# biochem.net
KiCad netlist of a schematic drawn in EAGLE
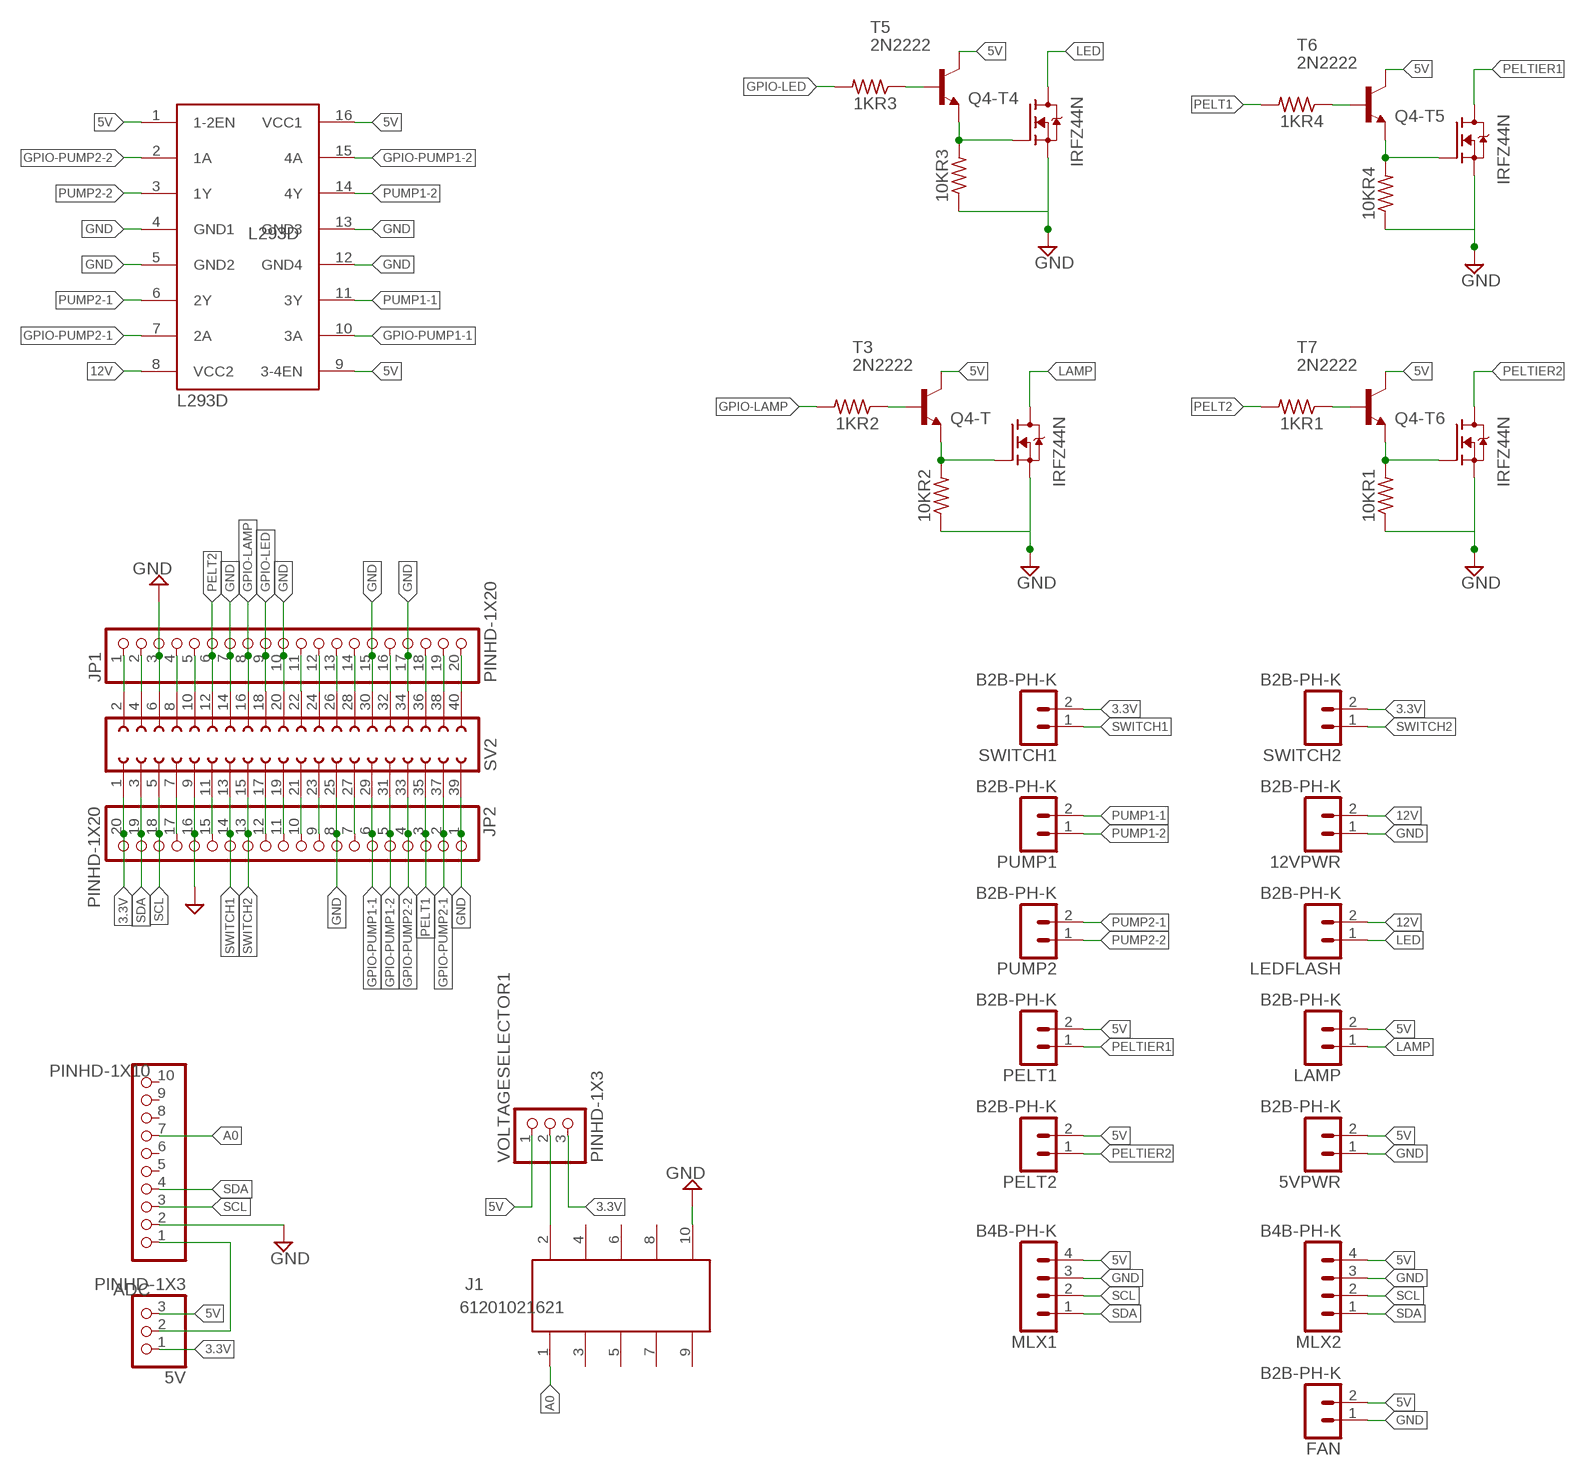
[diagram p0: schematic, sheet 1]

(export (version "E")
  (design (tool "Eeschema 10.0.6"))
  (components
    (comp (ref "1KR1")
      (value "R-US_0204/7")
      (footprint "eagle-import:0204_7")
      (libsource (lib "eagle-import") (part "R-US_0204/7"))
    )
    (comp (ref "1KR2")
      (value "R-US_0204/7")
      (footprint "eagle-import:0204_7")
      (libsource (lib "eagle-import") (part "R-US_0204/7"))
    )
    (comp (ref "1KR3")
      (value "R-US_0204/7")
      (footprint "eagle-import:0204_7")
      (libsource (lib "eagle-import") (part "R-US_0204/7"))
    )
    (comp (ref "1KR4")
      (value "R-US_0204/7")
      (footprint "eagle-import:0204_7")
      (libsource (lib "eagle-import") (part "R-US_0204/7"))
    )
    (comp (ref "5V")
      (value "PINHD-1X3")
      (footprint "eagle-import:1X03")
      (libsource (lib "eagle-import") (part "PINHD-1X3"))
    )
    (comp (ref "5VPWR")
      (value "B2B-PH-K")
      (footprint "eagle-import:B2B-PH-K")
      (fields (field (name "MF") "JST Corporation"))
      (libsource (lib "eagle-import") (part "B2B-PH-K"))
    )
    (comp (ref "10KR1")
      (value "R-US_0204/7")
      (footprint "eagle-import:0204_7")
      (libsource (lib "eagle-import") (part "R-US_0204/7"))
    )
    (comp (ref "10KR2")
      (value "R-US_0204/7")
      (footprint "eagle-import:0204_7")
      (libsource (lib "eagle-import") (part "R-US_0204/7"))
    )
    (comp (ref "10KR3")
      (value "R-US_0204/7")
      (footprint "eagle-import:0204_7")
      (libsource (lib "eagle-import") (part "R-US_0204/7"))
    )
    (comp (ref "10KR4")
      (value "R-US_0204/7")
      (footprint "eagle-import:0204_7")
      (libsource (lib "eagle-import") (part "R-US_0204/7"))
    )
    (comp (ref "12VPWR")
      (value "B2B-PH-K")
      (footprint "eagle-import:B2B-PH-K")
      (fields (field (name "MF") "JST Corporation"))
      (libsource (lib "eagle-import") (part "B2B-PH-K"))
    )
    (comp (ref "ADC")
      (value "PINHD-1X10")
      (footprint "eagle-import:1X10")
      (libsource (lib "eagle-import") (part "PINHD-1X10"))
    )
    (comp (ref "FAN")
      (value "B2B-PH-K")
      (footprint "eagle-import:B2B-PH-K")
      (fields (field (name "MF") "JST Corporation"))
      (libsource (lib "eagle-import") (part "B2B-PH-K"))
    )
    (comp (ref "J1")
      (value "61201021621")
      (footprint "eagle-import:61201021621")
      (fields (field (name "MF") "Wurth Elektronik"))
      (libsource (lib "eagle-import") (part "61201021621"))
    )
    (comp (ref "JP1")
      (value "PINHD-1X20")
      (footprint "eagle-import:1X20")
      (libsource (lib "eagle-import") (part "PINHD-1X20"))
    )
    (comp (ref "JP2")
      (value "PINHD-1X20")
      (footprint "eagle-import:1X20")
      (libsource (lib "eagle-import") (part "PINHD-1X20"))
    )
    (comp (ref "L293D")
      (value "L293D")
      (footprint "eagle-import:DIL16")
      (libsource (lib "eagle-import") (part "L293D"))
    )
    (comp (ref "LAMP")
      (value "B2B-PH-K")
      (footprint "eagle-import:B2B-PH-K")
      (fields (field (name "MF") "JST Corporation"))
      (libsource (lib "eagle-import") (part "B2B-PH-K"))
    )
    (comp (ref "LEDFLASH")
      (value "B2B-PH-K")
      (footprint "eagle-import:B2B-PH-K")
      (fields (field (name "MF") "JST Corporation"))
      (libsource (lib "eagle-import") (part "B2B-PH-K"))
    )
    (comp (ref "MLX1")
      (value "B4B-PH-K")
      (footprint "eagle-import:B4B-PH-K")
      (libsource (lib "eagle-import") (part "B4B-PH-K"))
    )
    (comp (ref "MLX2")
      (value "B4B-PH-K")
      (footprint "eagle-import:B4B-PH-K")
      (libsource (lib "eagle-import") (part "B4B-PH-K"))
    )
    (comp (ref "PELT1")
      (value "B2B-PH-K")
      (footprint "eagle-import:B2B-PH-K")
      (fields (field (name "MF") "JST Corporation"))
      (libsource (lib "eagle-import") (part "B2B-PH-K"))
    )
    (comp (ref "PELT2")
      (value "B2B-PH-K")
      (footprint "eagle-import:B2B-PH-K")
      (fields (field (name "MF") "JST Corporation"))
      (libsource (lib "eagle-import") (part "B2B-PH-K"))
    )
    (comp (ref "PUMP1")
      (value "B2B-PH-K")
      (footprint "eagle-import:B2B-PH-K")
      (fields (field (name "MF") "JST Corporation"))
      (libsource (lib "eagle-import") (part "B2B-PH-K"))
    )
    (comp (ref "PUMP2")
      (value "B2B-PH-K")
      (footprint "eagle-import:B2B-PH-K")
      (fields (field (name "MF") "JST Corporation"))
      (libsource (lib "eagle-import") (part "B2B-PH-K"))
    )
    (comp (ref "Q4-T")
      (value "IRFZ44N")
      (footprint "eagle-import:TO254P1016X419X2286-3")
      (fields (field (name "MF") "Infineon Technologies"))
      (libsource (lib "eagle-import") (part "IRFZ44N"))
    )
    (comp (ref "Q4-T4")
      (value "IRFZ44N")
      (footprint "eagle-import:TO254P1016X419X2286-3")
      (fields (field (name "MF") "Infineon Technologies"))
      (libsource (lib "eagle-import") (part "IRFZ44N"))
    )
    (comp (ref "Q4-T5")
      (value "IRFZ44N")
      (footprint "eagle-import:TO254P1016X419X2286-3")
      (fields (field (name "MF") "Infineon Technologies"))
      (libsource (lib "eagle-import") (part "IRFZ44N"))
    )
    (comp (ref "Q4-T6")
      (value "IRFZ44N")
      (footprint "eagle-import:TO254P1016X419X2286-3")
      (fields (field (name "MF") "Infineon Technologies"))
      (libsource (lib "eagle-import") (part "IRFZ44N"))
    )
    (comp (ref "SV2")
      (value "FE20-2")
      (footprint "eagle-import:FE20-2")
      (libsource (lib "eagle-import") (part "FE20-2"))
    )
    (comp (ref "SWITCH1")
      (value "B2B-PH-K")
      (footprint "eagle-import:B2B-PH-K")
      (fields (field (name "MF") "JST Corporation"))
      (libsource (lib "eagle-import") (part "B2B-PH-K"))
    )
    (comp (ref "SWITCH2")
      (value "B2B-PH-K")
      (footprint "eagle-import:B2B-PH-K")
      (fields (field (name "MF") "JST Corporation"))
      (libsource (lib "eagle-import") (part "B2B-PH-K"))
    )
    (comp (ref "T3")
      (value "2N2222")
      (footprint "eagle-import:TO92-EBC-OVAL")
      (libsource (lib "eagle-import") (part "2N2222"))
    )
    (comp (ref "T5")
      (value "2N2222")
      (footprint "eagle-import:TO92-EBC-OVAL")
      (libsource (lib "eagle-import") (part "2N2222"))
    )
    (comp (ref "T6")
      (value "2N2222")
      (footprint "eagle-import:TO92-EBC-OVAL")
      (libsource (lib "eagle-import") (part "2N2222"))
    )
    (comp (ref "T7")
      (value "2N2222")
      (footprint "eagle-import:TO92-EBC-OVAL")
      (libsource (lib "eagle-import") (part "2N2222"))
    )
    (comp (ref "VOLTAGESELECTOR1")
      (value "PINHD-1X3")
      (footprint "eagle-import:1X03")
      (libsource (lib "eagle-import") (part "PINHD-1X3"))
    )
  )
  (nets
    (net (code "1") (name "3.3V") (class "Default")
      (node (ref "5V") (pin "1") (pinfunction "1_1") (pintype "passive"))
      (node (ref "JP2") (pin "20") (pinfunction "20_20") (pintype "passive"))
      (node (ref "SV2") (pin "1") (pinfunction "1_1") (pintype "passive"))
      (node (ref "SWITCH1") (pin "2") (pinfunction "2_2") (pintype "passive"))
      (node (ref "SWITCH2") (pin "2") (pinfunction "2_2") (pintype "passive"))
      (node (ref "VOLTAGESELECTOR1") (pin "3") (pinfunction "3_3") (pintype "passive"))
    )
    (net (code "2") (name "5V") (class "Default")
      (node (ref "5V") (pin "3") (pinfunction "3_3") (pintype "passive"))
      (node (ref "5VPWR") (pin "2") (pinfunction "2_2") (pintype "passive"))
      (node (ref "FAN") (pin "2") (pinfunction "2_2") (pintype "passive"))
      (node (ref "L293D") (pin "1") (pinfunction "1-2EN_1") (pintype "input"))
      (node (ref "L293D") (pin "16") (pinfunction "VCC1_16") (pintype "power_in"))
      (node (ref "L293D") (pin "9") (pinfunction "3-4EN_9") (pintype "input"))
      (node (ref "LAMP") (pin "2") (pinfunction "2_2") (pintype "passive"))
      (node (ref "MLX1") (pin "4") (pinfunction "4_4") (pintype "passive"))
      (node (ref "MLX2") (pin "4") (pinfunction "4_4") (pintype "passive"))
      (node (ref "PELT1") (pin "2") (pinfunction "2_2") (pintype "passive"))
      (node (ref "PELT2") (pin "2") (pinfunction "2_2") (pintype "passive"))
      (node (ref "T3") (pin "C") (pinfunction "C_C") (pintype "passive"))
      (node (ref "T5") (pin "C") (pinfunction "C_C") (pintype "passive"))
      (node (ref "T6") (pin "C") (pinfunction "C_C") (pintype "passive"))
      (node (ref "T7") (pin "C") (pinfunction "C_C") (pintype "passive"))
      (node (ref "VOLTAGESELECTOR1") (pin "1") (pinfunction "1_1") (pintype "passive"))
    )
    (net (code "3") (name "12V") (class "Default")
      (node (ref "12VPWR") (pin "2") (pinfunction "2_2") (pintype "passive"))
      (node (ref "L293D") (pin "8") (pinfunction "VCC2_8") (pintype "power_in"))
      (node (ref "LEDFLASH") (pin "2") (pinfunction "2_2") (pintype "passive"))
    )
    (net (code "4") (name "A0") (class "Default")
      (node (ref "ADC") (pin "7") (pinfunction "7_7") (pintype "passive"))
      (node (ref "J1") (pin "1") (pinfunction "1_1") (pintype "passive"))
    )
    (net (code "5") (name "GND") (class "Default")
      (node (ref "10KR1") (pin "1") (pinfunction "1_1") (pintype "passive"))
      (node (ref "10KR2") (pin "1") (pinfunction "1_1") (pintype "passive"))
      (node (ref "10KR3") (pin "1") (pinfunction "1_1") (pintype "passive"))
      (node (ref "10KR4") (pin "1") (pinfunction "1_1") (pintype "passive"))
      (node (ref "12VPWR") (pin "1") (pinfunction "1_1") (pintype "passive"))
      (node (ref "5VPWR") (pin "1") (pinfunction "1_1") (pintype "passive"))
      (node (ref "ADC") (pin "2") (pinfunction "2_2") (pintype "passive"))
      (node (ref "FAN") (pin "1") (pinfunction "1_1") (pintype "passive"))
      (node (ref "J1") (pin "10") (pinfunction "10_10") (pintype "passive"))
      (node (ref "JP1") (pin "10") (pinfunction "10_10") (pintype "passive"))
      (node (ref "JP1") (pin "15") (pinfunction "15_15") (pintype "passive"))
      (node (ref "JP1") (pin "17") (pinfunction "17_17") (pintype "passive"))
      (node (ref "JP1") (pin "3") (pinfunction "3_3") (pintype "passive"))
      (node (ref "JP1") (pin "7") (pinfunction "7_7") (pintype "passive"))
      (node (ref "JP2") (pin "1") (pinfunction "1_1") (pintype "passive"))
      (node (ref "JP2") (pin "16") (pinfunction "16_16") (pintype "passive"))
      (node (ref "JP2") (pin "8") (pinfunction "8_8") (pintype "passive"))
      (node (ref "L293D") (pin "12") (pinfunction "GND4_12") (pintype "power_in"))
      (node (ref "L293D") (pin "13") (pinfunction "GND3_13") (pintype "power_in"))
      (node (ref "L293D") (pin "4") (pinfunction "GND1_4") (pintype "power_in"))
      (node (ref "L293D") (pin "5") (pinfunction "GND2_5") (pintype "power_in"))
      (node (ref "MLX1") (pin "3") (pinfunction "3_3") (pintype "passive"))
      (node (ref "MLX2") (pin "3") (pinfunction "3_3") (pintype "passive"))
      (node (ref "Q4-T") (pin "3") (pinfunction "S_3") (pintype "passive"))
      (node (ref "Q4-T4") (pin "3") (pinfunction "S_3") (pintype "passive"))
      (node (ref "Q4-T5") (pin "3") (pinfunction "S_3") (pintype "passive"))
      (node (ref "Q4-T6") (pin "3") (pinfunction "S_3") (pintype "passive"))
      (node (ref "SV2") (pin "14") (pinfunction "14_14") (pintype "passive"))
      (node (ref "SV2") (pin "20") (pinfunction "20_20") (pintype "passive"))
      (node (ref "SV2") (pin "25") (pinfunction "25_25") (pintype "passive"))
      (node (ref "SV2") (pin "30") (pinfunction "30_30") (pintype "passive"))
      (node (ref "SV2") (pin "34") (pinfunction "34_34") (pintype "passive"))
      (node (ref "SV2") (pin "39") (pinfunction "39_39") (pintype "passive"))
      (node (ref "SV2") (pin "6") (pinfunction "6_6") (pintype "passive"))
      (node (ref "SV2") (pin "9") (pinfunction "9_9") (pintype "passive"))
    )
    (net (code "6") (name "GPIO-LAMP") (class "Default")
      (node (ref "1KR2") (pin "2") (pinfunction "2_2") (pintype "passive"))
      (node (ref "JP1") (pin "8") (pinfunction "8_8") (pintype "passive"))
      (node (ref "SV2") (pin "16") (pinfunction "16_16") (pintype "passive"))
    )
    (net (code "7") (name "GPIO-LED") (class "Default")
      (node (ref "1KR3") (pin "2") (pinfunction "2_2") (pintype "passive"))
      (node (ref "JP1") (pin "9") (pinfunction "9_9") (pintype "passive"))
      (node (ref "SV2") (pin "18") (pinfunction "18_18") (pintype "passive"))
    )
    (net (code "8") (name "GPIO-PUMP1-1") (class "Default")
      (node (ref "JP2") (pin "6") (pinfunction "6_6") (pintype "passive"))
      (node (ref "L293D") (pin "10") (pinfunction "3A_10") (pintype "input"))
      (node (ref "SV2") (pin "29") (pinfunction "29_29") (pintype "passive"))
    )
    (net (code "9") (name "GPIO-PUMP1-2") (class "Default")
      (node (ref "JP2") (pin "5") (pinfunction "5_5") (pintype "passive"))
      (node (ref "L293D") (pin "15") (pinfunction "4A_15") (pintype "input"))
      (node (ref "SV2") (pin "31") (pinfunction "31_31") (pintype "passive"))
    )
    (net (code "10") (name "GPIO-PUMP2-1") (class "Default")
      (node (ref "JP2") (pin "2") (pinfunction "2_2") (pintype "passive"))
      (node (ref "L293D") (pin "7") (pinfunction "2A_7") (pintype "input"))
      (node (ref "SV2") (pin "37") (pinfunction "37_37") (pintype "passive"))
    )
    (net (code "11") (name "GPIO-PUMP2-2") (class "Default")
      (node (ref "JP2") (pin "4") (pinfunction "4_4") (pintype "passive"))
      (node (ref "L293D") (pin "2") (pinfunction "1A_2") (pintype "input"))
      (node (ref "SV2") (pin "33") (pinfunction "33_33") (pintype "passive"))
    )
    (net (code "12") (name "LAMP") (class "Default")
      (node (ref "LAMP") (pin "1") (pinfunction "1_1") (pintype "passive"))
      (node (ref "Q4-T") (pin "2") (pinfunction "D_2") (pintype "passive"))
    )
    (net (code "13") (name "LED") (class "Default")
      (node (ref "LEDFLASH") (pin "1") (pinfunction "1_1") (pintype "passive"))
      (node (ref "Q4-T4") (pin "2") (pinfunction "D_2") (pintype "passive"))
    )
    (net (code "14") (name "Net-(1KR1-Pad1)") (class "Default")
      (node (ref "1KR1") (pin "1") (pinfunction "1_1") (pintype "passive"))
      (node (ref "T7") (pin "B") (pinfunction "B_B") (pintype "passive"))
    )
    (net (code "15") (name "Net-(1KR2-Pad1)") (class "Default")
      (node (ref "1KR2") (pin "1") (pinfunction "1_1") (pintype "passive"))
      (node (ref "T3") (pin "B") (pinfunction "B_B") (pintype "passive"))
    )
    (net (code "16") (name "Net-(1KR3-Pad1)") (class "Default")
      (node (ref "1KR3") (pin "1") (pinfunction "1_1") (pintype "passive"))
      (node (ref "T5") (pin "B") (pinfunction "B_B") (pintype "passive"))
    )
    (net (code "17") (name "Net-(1KR4-Pad1)") (class "Default")
      (node (ref "1KR4") (pin "1") (pinfunction "1_1") (pintype "passive"))
      (node (ref "T6") (pin "B") (pinfunction "B_B") (pintype "passive"))
    )
    (net (code "18") (name "Net-(5V-Pad2)") (class "Default")
      (node (ref "5V") (pin "2") (pinfunction "2_2") (pintype "passive"))
      (node (ref "ADC") (pin "1") (pinfunction "1_1") (pintype "passive"))
    )
    (net (code "19") (name "Net-(J1-Pad2)") (class "Default")
      (node (ref "J1") (pin "2") (pinfunction "2_2") (pintype "passive"))
      (node (ref "VOLTAGESELECTOR1") (pin "2") (pinfunction "2_2") (pintype "passive"))
    )
    (net (code "20") (name "Net-(JP1-Pad1)") (class "Default")
      (node (ref "JP1") (pin "1") (pinfunction "1_1") (pintype "passive"))
      (node (ref "SV2") (pin "2") (pinfunction "2_2") (pintype "passive"))
    )
    (net (code "21") (name "Net-(JP1-Pad2)") (class "Default")
      (node (ref "JP1") (pin "2") (pinfunction "2_2") (pintype "passive"))
      (node (ref "SV2") (pin "4") (pinfunction "4_4") (pintype "passive"))
    )
    (net (code "22") (name "Net-(JP1-Pad4)") (class "Default")
      (node (ref "JP1") (pin "4") (pinfunction "4_4") (pintype "passive"))
      (node (ref "SV2") (pin "8") (pinfunction "8_8") (pintype "passive"))
    )
    (net (code "23") (name "Net-(JP1-Pad5)") (class "Default")
      (node (ref "JP1") (pin "5") (pinfunction "5_5") (pintype "passive"))
      (node (ref "SV2") (pin "10") (pinfunction "10_10") (pintype "passive"))
    )
    (net (code "24") (name "Net-(JP1-Pad11)") (class "Default")
      (node (ref "JP1") (pin "11") (pinfunction "11_11") (pintype "passive"))
      (node (ref "SV2") (pin "22") (pinfunction "22_22") (pintype "passive"))
    )
    (net (code "25") (name "Net-(JP1-Pad12)") (class "Default")
      (node (ref "JP1") (pin "12") (pinfunction "12_12") (pintype "passive"))
      (node (ref "SV2") (pin "24") (pinfunction "24_24") (pintype "passive"))
    )
    (net (code "26") (name "Net-(JP1-Pad13)") (class "Default")
      (node (ref "JP1") (pin "13") (pinfunction "13_13") (pintype "passive"))
      (node (ref "SV2") (pin "26") (pinfunction "26_26") (pintype "passive"))
    )
    (net (code "27") (name "Net-(JP1-Pad14)") (class "Default")
      (node (ref "JP1") (pin "14") (pinfunction "14_14") (pintype "passive"))
      (node (ref "SV2") (pin "28") (pinfunction "28_28") (pintype "passive"))
    )
    (net (code "28") (name "Net-(JP1-Pad16)") (class "Default")
      (node (ref "JP1") (pin "16") (pinfunction "16_16") (pintype "passive"))
      (node (ref "SV2") (pin "32") (pinfunction "32_32") (pintype "passive"))
    )
    (net (code "29") (name "Net-(JP1-Pad18)") (class "Default")
      (node (ref "JP1") (pin "18") (pinfunction "18_18") (pintype "passive"))
      (node (ref "SV2") (pin "36") (pinfunction "36_36") (pintype "passive"))
    )
    (net (code "30") (name "Net-(JP1-Pad19)") (class "Default")
      (node (ref "JP1") (pin "19") (pinfunction "19_19") (pintype "passive"))
      (node (ref "SV2") (pin "38") (pinfunction "38_38") (pintype "passive"))
    )
    (net (code "31") (name "Net-(JP1-Pad20)") (class "Default")
      (node (ref "JP1") (pin "20") (pinfunction "20_20") (pintype "passive"))
      (node (ref "SV2") (pin "40") (pinfunction "40_40") (pintype "passive"))
    )
    (net (code "32") (name "Net-(JP2-Pad7)") (class "Default")
      (node (ref "JP2") (pin "7") (pinfunction "7_7") (pintype "passive"))
      (node (ref "SV2") (pin "27") (pinfunction "27_27") (pintype "passive"))
    )
    (net (code "33") (name "Net-(JP2-Pad9)") (class "Default")
      (node (ref "JP2") (pin "9") (pinfunction "9_9") (pintype "passive"))
      (node (ref "SV2") (pin "23") (pinfunction "23_23") (pintype "passive"))
    )
    (net (code "34") (name "Net-(JP2-Pad10)") (class "Default")
      (node (ref "JP2") (pin "10") (pinfunction "10_10") (pintype "passive"))
      (node (ref "SV2") (pin "21") (pinfunction "21_21") (pintype "passive"))
    )
    (net (code "35") (name "Net-(JP2-Pad11)") (class "Default")
      (node (ref "JP2") (pin "11") (pinfunction "11_11") (pintype "passive"))
      (node (ref "SV2") (pin "19") (pinfunction "19_19") (pintype "passive"))
    )
    (net (code "36") (name "Net-(JP2-Pad12)") (class "Default")
      (node (ref "JP2") (pin "12") (pinfunction "12_12") (pintype "passive"))
      (node (ref "SV2") (pin "17") (pinfunction "17_17") (pintype "passive"))
    )
    (net (code "37") (name "Net-(JP2-Pad15)") (class "Default")
      (node (ref "JP2") (pin "15") (pinfunction "15_15") (pintype "passive"))
      (node (ref "SV2") (pin "11") (pinfunction "11_11") (pintype "passive"))
    )
    (net (code "38") (name "Net-(JP2-Pad17)") (class "Default")
      (node (ref "JP2") (pin "17") (pinfunction "17_17") (pintype "passive"))
      (node (ref "SV2") (pin "7") (pinfunction "7_7") (pintype "passive"))
    )
    (net (code "39") (name "Net-(Q4-T-G)") (class "Default")
      (node (ref "10KR2") (pin "2") (pinfunction "2_2") (pintype "passive"))
      (node (ref "Q4-T") (pin "1") (pinfunction "G_1") (pintype "passive"))
      (node (ref "T3") (pin "E") (pinfunction "E_E") (pintype "passive"))
    )
    (net (code "40") (name "Net-(Q4-T4-G)") (class "Default")
      (node (ref "10KR3") (pin "2") (pinfunction "2_2") (pintype "passive"))
      (node (ref "Q4-T4") (pin "1") (pinfunction "G_1") (pintype "passive"))
      (node (ref "T5") (pin "E") (pinfunction "E_E") (pintype "passive"))
    )
    (net (code "41") (name "Net-(Q4-T5-G)") (class "Default")
      (node (ref "10KR4") (pin "2") (pinfunction "2_2") (pintype "passive"))
      (node (ref "Q4-T5") (pin "1") (pinfunction "G_1") (pintype "passive"))
      (node (ref "T6") (pin "E") (pinfunction "E_E") (pintype "passive"))
    )
    (net (code "42") (name "Net-(Q4-T6-G)") (class "Default")
      (node (ref "10KR1") (pin "2") (pinfunction "2_2") (pintype "passive"))
      (node (ref "Q4-T6") (pin "1") (pinfunction "G_1") (pintype "passive"))
      (node (ref "T7") (pin "E") (pinfunction "E_E") (pintype "passive"))
    )
    (net (code "43") (name "PELT1") (class "Default")
      (node (ref "1KR4") (pin "2") (pinfunction "2_2") (pintype "passive"))
      (node (ref "JP2") (pin "3") (pinfunction "3_3") (pintype "passive"))
      (node (ref "SV2") (pin "35") (pinfunction "35_35") (pintype "passive"))
    )
    (net (code "44") (name "PELT2") (class "Default")
      (node (ref "1KR1") (pin "2") (pinfunction "2_2") (pintype "passive"))
      (node (ref "JP1") (pin "6") (pinfunction "6_6") (pintype "passive"))
      (node (ref "SV2") (pin "12") (pinfunction "12_12") (pintype "passive"))
    )
    (net (code "45") (name "PELTIER1") (class "Default")
      (node (ref "PELT1") (pin "1") (pinfunction "1_1") (pintype "passive"))
      (node (ref "Q4-T5") (pin "2") (pinfunction "D_2") (pintype "passive"))
    )
    (net (code "46") (name "PELTIER2") (class "Default")
      (node (ref "PELT2") (pin "1") (pinfunction "1_1") (pintype "passive"))
      (node (ref "Q4-T6") (pin "2") (pinfunction "D_2") (pintype "passive"))
    )
    (net (code "47") (name "PUMP1-1") (class "Default")
      (node (ref "L293D") (pin "11") (pinfunction "3Y_11") (pintype "output"))
      (node (ref "PUMP1") (pin "2") (pinfunction "2_2") (pintype "passive"))
    )
    (net (code "48") (name "PUMP1-2") (class "Default")
      (node (ref "L293D") (pin "14") (pinfunction "4Y_14") (pintype "output"))
      (node (ref "PUMP1") (pin "1") (pinfunction "1_1") (pintype "passive"))
    )
    (net (code "49") (name "PUMP2-1") (class "Default")
      (node (ref "L293D") (pin "6") (pinfunction "2Y_6") (pintype "output"))
      (node (ref "PUMP2") (pin "2") (pinfunction "2_2") (pintype "passive"))
    )
    (net (code "50") (name "PUMP2-2") (class "Default")
      (node (ref "L293D") (pin "3") (pinfunction "1Y_3") (pintype "output"))
      (node (ref "PUMP2") (pin "1") (pinfunction "1_1") (pintype "passive"))
    )
    (net (code "51") (name "SCL") (class "Default")
      (node (ref "ADC") (pin "3") (pinfunction "3_3") (pintype "passive"))
      (node (ref "JP2") (pin "18") (pinfunction "18_18") (pintype "passive"))
      (node (ref "MLX1") (pin "2") (pinfunction "2_2") (pintype "passive"))
      (node (ref "MLX2") (pin "2") (pinfunction "2_2") (pintype "passive"))
      (node (ref "SV2") (pin "5") (pinfunction "5_5") (pintype "passive"))
    )
    (net (code "52") (name "SDA") (class "Default")
      (node (ref "ADC") (pin "4") (pinfunction "4_4") (pintype "passive"))
      (node (ref "JP2") (pin "19") (pinfunction "19_19") (pintype "passive"))
      (node (ref "MLX1") (pin "1") (pinfunction "1_1") (pintype "passive"))
      (node (ref "MLX2") (pin "1") (pinfunction "1_1") (pintype "passive"))
      (node (ref "SV2") (pin "3") (pinfunction "3_3") (pintype "passive"))
    )
    (net (code "53") (name "SWITCH1") (class "Default")
      (node (ref "JP2") (pin "14") (pinfunction "14_14") (pintype "passive"))
      (node (ref "SV2") (pin "13") (pinfunction "13_13") (pintype "passive"))
      (node (ref "SWITCH1") (pin "1") (pinfunction "1_1") (pintype "passive"))
    )
    (net (code "54") (name "SWITCH2") (class "Default")
      (node (ref "JP2") (pin "13") (pinfunction "13_13") (pintype "passive"))
      (node (ref "SV2") (pin "15") (pinfunction "15_15") (pintype "passive"))
      (node (ref "SWITCH2") (pin "1") (pinfunction "1_1") (pintype "passive"))
    )
    (net (code "55") (name "unconnected-(ADC-Pad5)") (class "Default")
      (node (ref "ADC") (pin "5") (pinfunction "5_5") (pintype "passive"))
    )
    (net (code "56") (name "unconnected-(ADC-Pad6)") (class "Default")
      (node (ref "ADC") (pin "6") (pinfunction "6_6") (pintype "passive"))
    )
    (net (code "57") (name "unconnected-(ADC-Pad8)") (class "Default")
      (node (ref "ADC") (pin "8") (pinfunction "8_8") (pintype "passive"))
    )
    (net (code "58") (name "unconnected-(ADC-Pad9)") (class "Default")
      (node (ref "ADC") (pin "9") (pinfunction "9_9") (pintype "passive"))
    )
    (net (code "59") (name "unconnected-(ADC-Pad10)") (class "Default")
      (node (ref "ADC") (pin "10") (pinfunction "10_10") (pintype "passive"))
    )
    (net (code "60") (name "unconnected-(J1-Pad3)") (class "Default")
      (node (ref "J1") (pin "3") (pinfunction "3_3") (pintype "passive"))
    )
    (net (code "61") (name "unconnected-(J1-Pad4)") (class "Default")
      (node (ref "J1") (pin "4") (pinfunction "4_4") (pintype "passive"))
    )
    (net (code "62") (name "unconnected-(J1-Pad5)") (class "Default")
      (node (ref "J1") (pin "5") (pinfunction "5_5") (pintype "passive"))
    )
    (net (code "63") (name "unconnected-(J1-Pad6)") (class "Default")
      (node (ref "J1") (pin "6") (pinfunction "6_6") (pintype "passive"))
    )
    (net (code "64") (name "unconnected-(J1-Pad7)") (class "Default")
      (node (ref "J1") (pin "7") (pinfunction "7_7") (pintype "passive"))
    )
    (net (code "65") (name "unconnected-(J1-Pad8)") (class "Default")
      (node (ref "J1") (pin "8") (pinfunction "8_8") (pintype "passive"))
    )
    (net (code "66") (name "unconnected-(J1-Pad9)") (class "Default")
      (node (ref "J1") (pin "9") (pinfunction "9_9") (pintype "passive"))
    )
  )
)
